# display.net
KiCad netlist of a schematic drawn in EAGLE
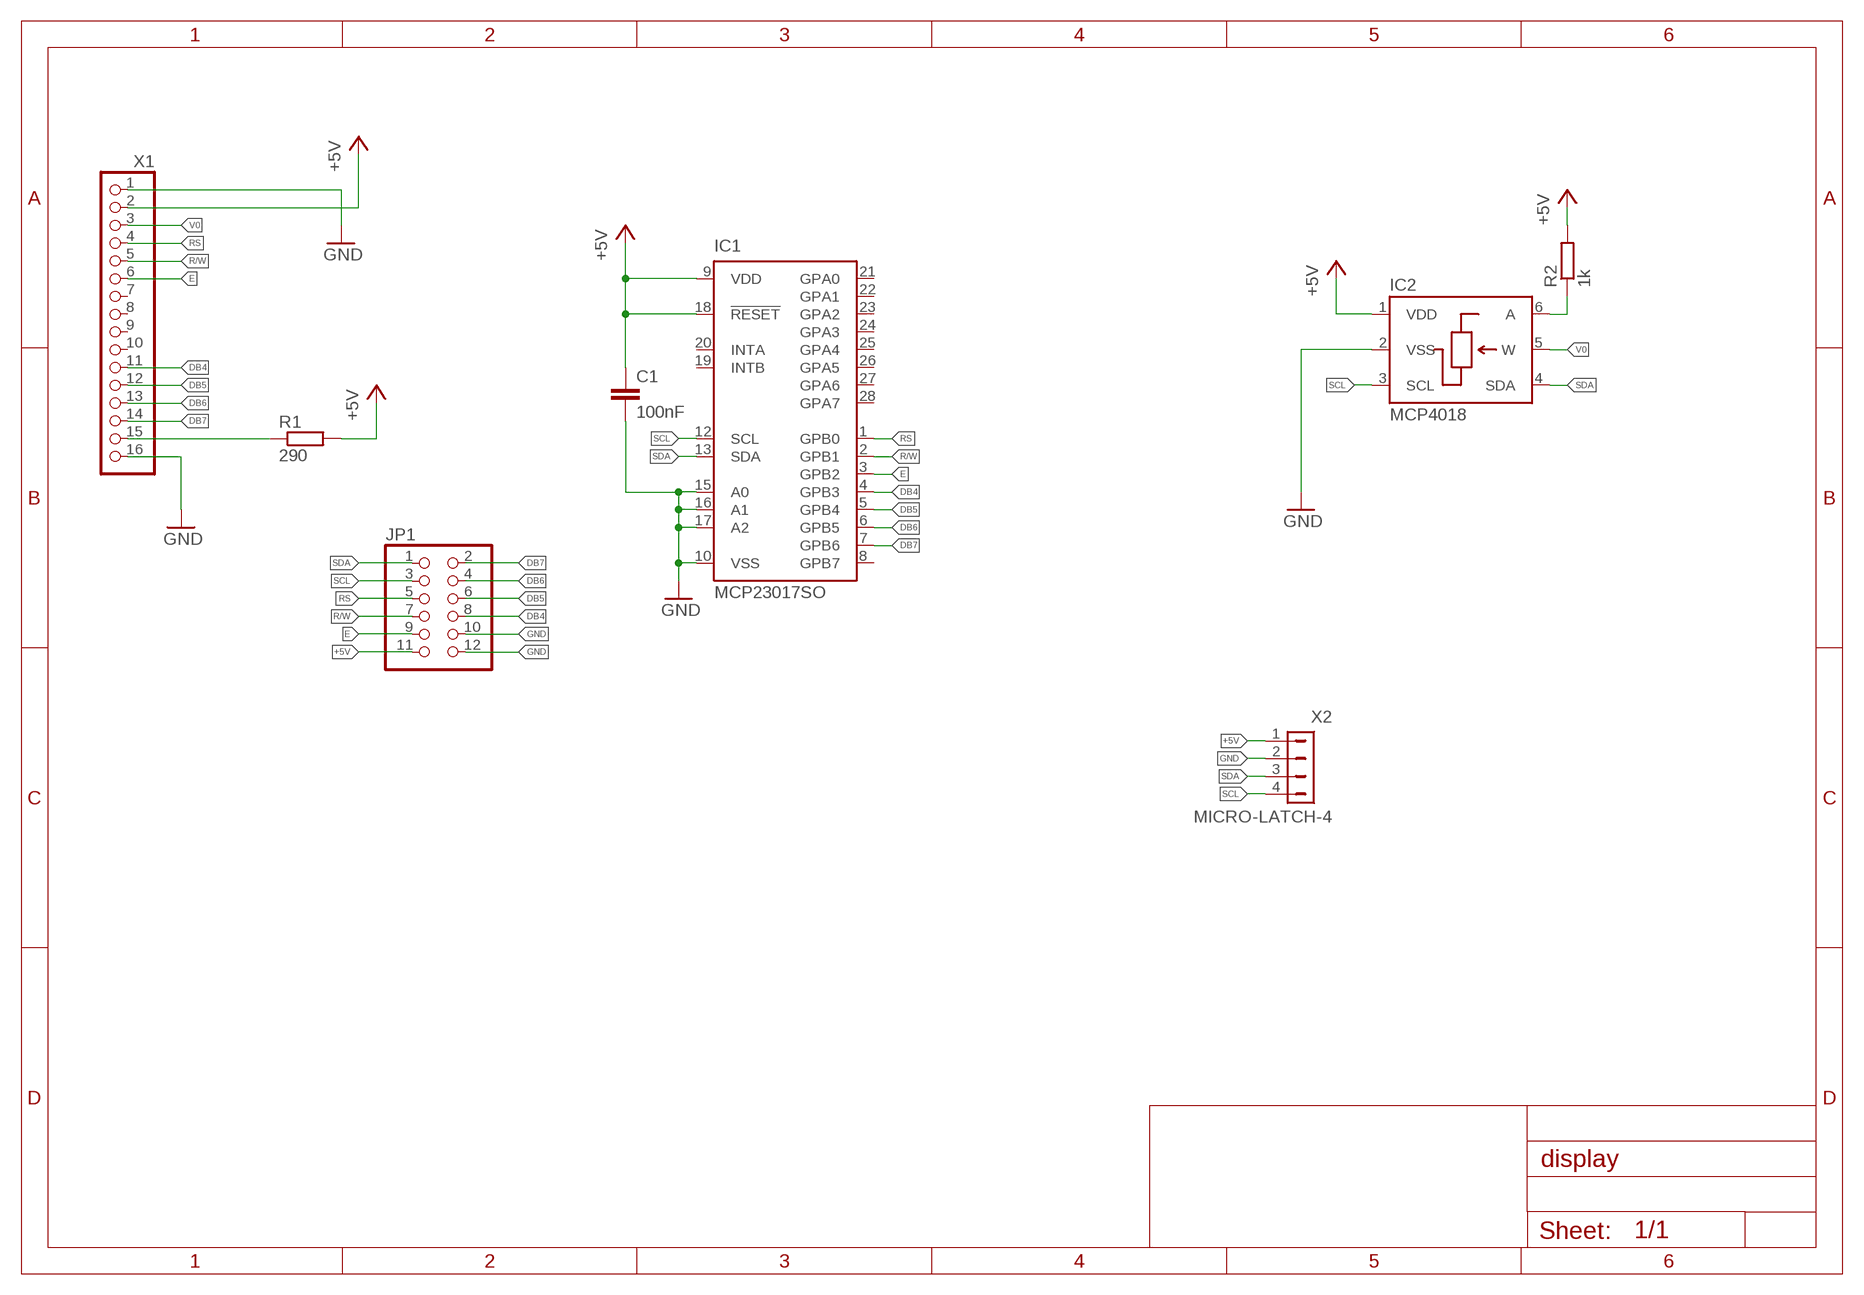
[diagram p0: schematic, sheet 1]

(export (version "E")
  (design (tool "Eeschema 10.0.6"))
  (components
    (comp (ref "C1")
      (value "100nF")
      (footprint "eagle-import:C0805")
      (libsource (lib "eagle-import") (part "C-EUC0805"))
    )
    (comp (ref "IC1")
      (value "MCP23017SO")
      (footprint "eagle-import:SO28W")
      (fields (field (name "MF") "MICROCHIP") (field (name "MPN") "MCP23017-E/SO"))
      (libsource (lib "eagle-import") (part "MCP23017SO"))
    )
    (comp (ref "IC2")
      (value "MCP4018")
      (footprint "eagle-import:SC70-6L")
      (libsource (lib "eagle-import") (part "MCP4018"))
    )
    (comp (ref "JP1")
      (value "PINHD-2X6")
      (footprint "eagle-import:2X06")
      (libsource (lib "eagle-import") (part "PINHD-2X6"))
    )
    (comp (ref "R1")
      (value "290")
      (footprint "eagle-import:R0805")
      (libsource (lib "eagle-import") (part "R-EU_R0805"))
    )
    (comp (ref "R2")
      (value "1k")
      (footprint "eagle-import:R0805")
      (libsource (lib "eagle-import") (part "R-EU_R0805"))
    )
    (comp (ref "X1")
      (value "PINHD-1X16")
      (footprint "eagle-import:1X16")
      (libsource (lib "eagle-import") (part "PINHD-1X16"))
    )
    (comp (ref "X2")
      (value "MICRO-LATCH-4")
      (footprint "eagle-import:MICRO-LATCH-4")
      (libsource (lib "eagle-import") (part "MICRO-LATCH-4"))
    )
  )
  (nets
    (net (code "1") (name "+5V") (class "Default")
      (node (ref "C1") (pin "1") (pinfunction "1_1") (pintype "passive"))
      (node (ref "IC1") (pin "18") (pinfunction "~{RESET}_18") (pintype "input"))
      (node (ref "IC1") (pin "9") (pinfunction "VDD_9") (pintype "power_in"))
      (node (ref "IC2") (pin "1") (pinfunction "VDD_1") (pintype "bidirectional"))
      (node (ref "JP1") (pin "11") (pinfunction "11_11") (pintype "passive"))
      (node (ref "R1") (pin "2") (pinfunction "2_2") (pintype "passive"))
      (node (ref "R2") (pin "2") (pinfunction "2_2") (pintype "passive"))
      (node (ref "X1") (pin "2") (pinfunction "2_2") (pintype "passive"))
      (node (ref "X2") (pin "1") (pinfunction "1_1") (pintype "passive"))
    )
    (net (code "2") (name "DB4") (class "Default")
      (node (ref "IC1") (pin "4") (pinfunction "GPB3_4") (pintype "bidirectional"))
      (node (ref "JP1") (pin "8") (pinfunction "8_8") (pintype "passive"))
      (node (ref "X1") (pin "11") (pinfunction "11_11") (pintype "passive"))
    )
    (net (code "3") (name "DB5") (class "Default")
      (node (ref "IC1") (pin "5") (pinfunction "GPB4_5") (pintype "bidirectional"))
      (node (ref "JP1") (pin "6") (pinfunction "6_6") (pintype "passive"))
      (node (ref "X1") (pin "12") (pinfunction "12_12") (pintype "passive"))
    )
    (net (code "4") (name "DB6") (class "Default")
      (node (ref "IC1") (pin "6") (pinfunction "GPB5_6") (pintype "bidirectional"))
      (node (ref "JP1") (pin "4") (pinfunction "4_4") (pintype "passive"))
      (node (ref "X1") (pin "13") (pinfunction "13_13") (pintype "passive"))
    )
    (net (code "5") (name "DB7") (class "Default")
      (node (ref "IC1") (pin "7") (pinfunction "GPB6_7") (pintype "bidirectional"))
      (node (ref "JP1") (pin "2") (pinfunction "2_2") (pintype "passive"))
      (node (ref "X1") (pin "14") (pinfunction "14_14") (pintype "passive"))
    )
    (net (code "6") (name "E") (class "Default")
      (node (ref "IC1") (pin "3") (pinfunction "GPB2_3") (pintype "bidirectional"))
      (node (ref "JP1") (pin "9") (pinfunction "9_9") (pintype "passive"))
      (node (ref "X1") (pin "6") (pinfunction "6_6") (pintype "passive"))
    )
    (net (code "7") (name "GND") (class "Default")
      (node (ref "C1") (pin "2") (pinfunction "2_2") (pintype "passive"))
      (node (ref "IC1") (pin "10") (pinfunction "VSS_10") (pintype "power_in"))
      (node (ref "IC1") (pin "15") (pinfunction "A0_15") (pintype "input"))
      (node (ref "IC1") (pin "16") (pinfunction "A1_16") (pintype "input"))
      (node (ref "IC1") (pin "17") (pinfunction "A2_17") (pintype "input"))
      (node (ref "IC2") (pin "2") (pinfunction "VSS_2") (pintype "bidirectional"))
      (node (ref "JP1") (pin "10") (pinfunction "10_10") (pintype "passive"))
      (node (ref "JP1") (pin "12") (pinfunction "12_12") (pintype "passive"))
      (node (ref "X1") (pin "1") (pinfunction "1_1") (pintype "passive"))
      (node (ref "X1") (pin "16") (pinfunction "16_16") (pintype "passive"))
      (node (ref "X2") (pin "2") (pinfunction "2_2") (pintype "passive"))
    )
    (net (code "8") (name "Net-(IC2-A)") (class "Default")
      (node (ref "IC2") (pin "6") (pinfunction "A_6") (pintype "bidirectional"))
      (node (ref "R2") (pin "1") (pinfunction "1_1") (pintype "passive"))
    )
    (net (code "9") (name "Net-(R1-Pad1)") (class "Default")
      (node (ref "R1") (pin "1") (pinfunction "1_1") (pintype "passive"))
      (node (ref "X1") (pin "15") (pinfunction "15_15") (pintype "passive"))
    )
    (net (code "10") (name "RS") (class "Default")
      (node (ref "IC1") (pin "1") (pinfunction "GPB0_1") (pintype "bidirectional"))
      (node (ref "JP1") (pin "5") (pinfunction "5_5") (pintype "passive"))
      (node (ref "X1") (pin "4") (pinfunction "4_4") (pintype "passive"))
    )
    (net (code "11") (name "R{slash}W") (class "Default")
      (node (ref "IC1") (pin "2") (pinfunction "GPB1_2") (pintype "bidirectional"))
      (node (ref "JP1") (pin "7") (pinfunction "7_7") (pintype "passive"))
      (node (ref "X1") (pin "5") (pinfunction "5_5") (pintype "passive"))
    )
    (net (code "12") (name "SCL") (class "Default")
      (node (ref "IC1") (pin "12") (pinfunction "SCL_12") (pintype "input"))
      (node (ref "IC2") (pin "3") (pinfunction "SCL_3") (pintype "bidirectional"))
      (node (ref "JP1") (pin "3") (pinfunction "3_3") (pintype "passive"))
      (node (ref "X2") (pin "4") (pinfunction "4_4") (pintype "passive"))
    )
    (net (code "13") (name "SDA") (class "Default")
      (node (ref "IC1") (pin "13") (pinfunction "SDA_13") (pintype "bidirectional"))
      (node (ref "IC2") (pin "4") (pinfunction "SDA_4") (pintype "bidirectional"))
      (node (ref "JP1") (pin "1") (pinfunction "1_1") (pintype "passive"))
      (node (ref "X2") (pin "3") (pinfunction "3_3") (pintype "passive"))
    )
    (net (code "14") (name "V0") (class "Default")
      (node (ref "IC2") (pin "5") (pinfunction "W_5") (pintype "bidirectional"))
      (node (ref "X1") (pin "3") (pinfunction "3_3") (pintype "passive"))
    )
    (net (code "15") (name "unconnected-(IC1-GPA0-Pad21)") (class "Default")
      (node (ref "IC1") (pin "21") (pinfunction "GPA0_21") (pintype "bidirectional"))
    )
    (net (code "16") (name "unconnected-(IC1-GPA1-Pad22)") (class "Default")
      (node (ref "IC1") (pin "22") (pinfunction "GPA1_22") (pintype "bidirectional"))
    )
    (net (code "17") (name "unconnected-(IC1-GPA2-Pad23)") (class "Default")
      (node (ref "IC1") (pin "23") (pinfunction "GPA2_23") (pintype "bidirectional"))
    )
    (net (code "18") (name "unconnected-(IC1-GPA3-Pad24)") (class "Default")
      (node (ref "IC1") (pin "24") (pinfunction "GPA3_24") (pintype "bidirectional"))
    )
    (net (code "19") (name "unconnected-(IC1-GPA4-Pad25)") (class "Default")
      (node (ref "IC1") (pin "25") (pinfunction "GPA4_25") (pintype "bidirectional"))
    )
    (net (code "20") (name "unconnected-(IC1-GPA5-Pad26)") (class "Default")
      (node (ref "IC1") (pin "26") (pinfunction "GPA5_26") (pintype "bidirectional"))
    )
    (net (code "21") (name "unconnected-(IC1-GPA6-Pad27)") (class "Default")
      (node (ref "IC1") (pin "27") (pinfunction "GPA6_27") (pintype "bidirectional"))
    )
    (net (code "22") (name "unconnected-(IC1-GPA7-Pad28)") (class "Default")
      (node (ref "IC1") (pin "28") (pinfunction "GPA7_28") (pintype "bidirectional"))
    )
    (net (code "23") (name "unconnected-(IC1-GPB7-Pad8)") (class "Default")
      (node (ref "IC1") (pin "8") (pinfunction "GPB7_8") (pintype "bidirectional"))
    )
    (net (code "24") (name "unconnected-(IC1-INTA-Pad20)") (class "Default")
      (node (ref "IC1") (pin "20") (pinfunction "INTA_20") (pintype "output"))
    )
    (net (code "25") (name "unconnected-(IC1-INTB-Pad19)") (class "Default")
      (node (ref "IC1") (pin "19") (pinfunction "INTB_19") (pintype "output"))
    )
    (net (code "26") (name "unconnected-(X1-Pad7)") (class "Default")
      (node (ref "X1") (pin "7") (pinfunction "7_7") (pintype "passive"))
    )
    (net (code "27") (name "unconnected-(X1-Pad8)") (class "Default")
      (node (ref "X1") (pin "8") (pinfunction "8_8") (pintype "passive"))
    )
    (net (code "28") (name "unconnected-(X1-Pad9)") (class "Default")
      (node (ref "X1") (pin "9") (pinfunction "9_9") (pintype "passive"))
    )
    (net (code "29") (name "unconnected-(X1-Pad10)") (class "Default")
      (node (ref "X1") (pin "10") (pinfunction "10_10") (pintype "passive"))
    )
  )
)
